# SUP_1_2_1_8.net
KiCad netlist of a schematic drawn in Altium Designer
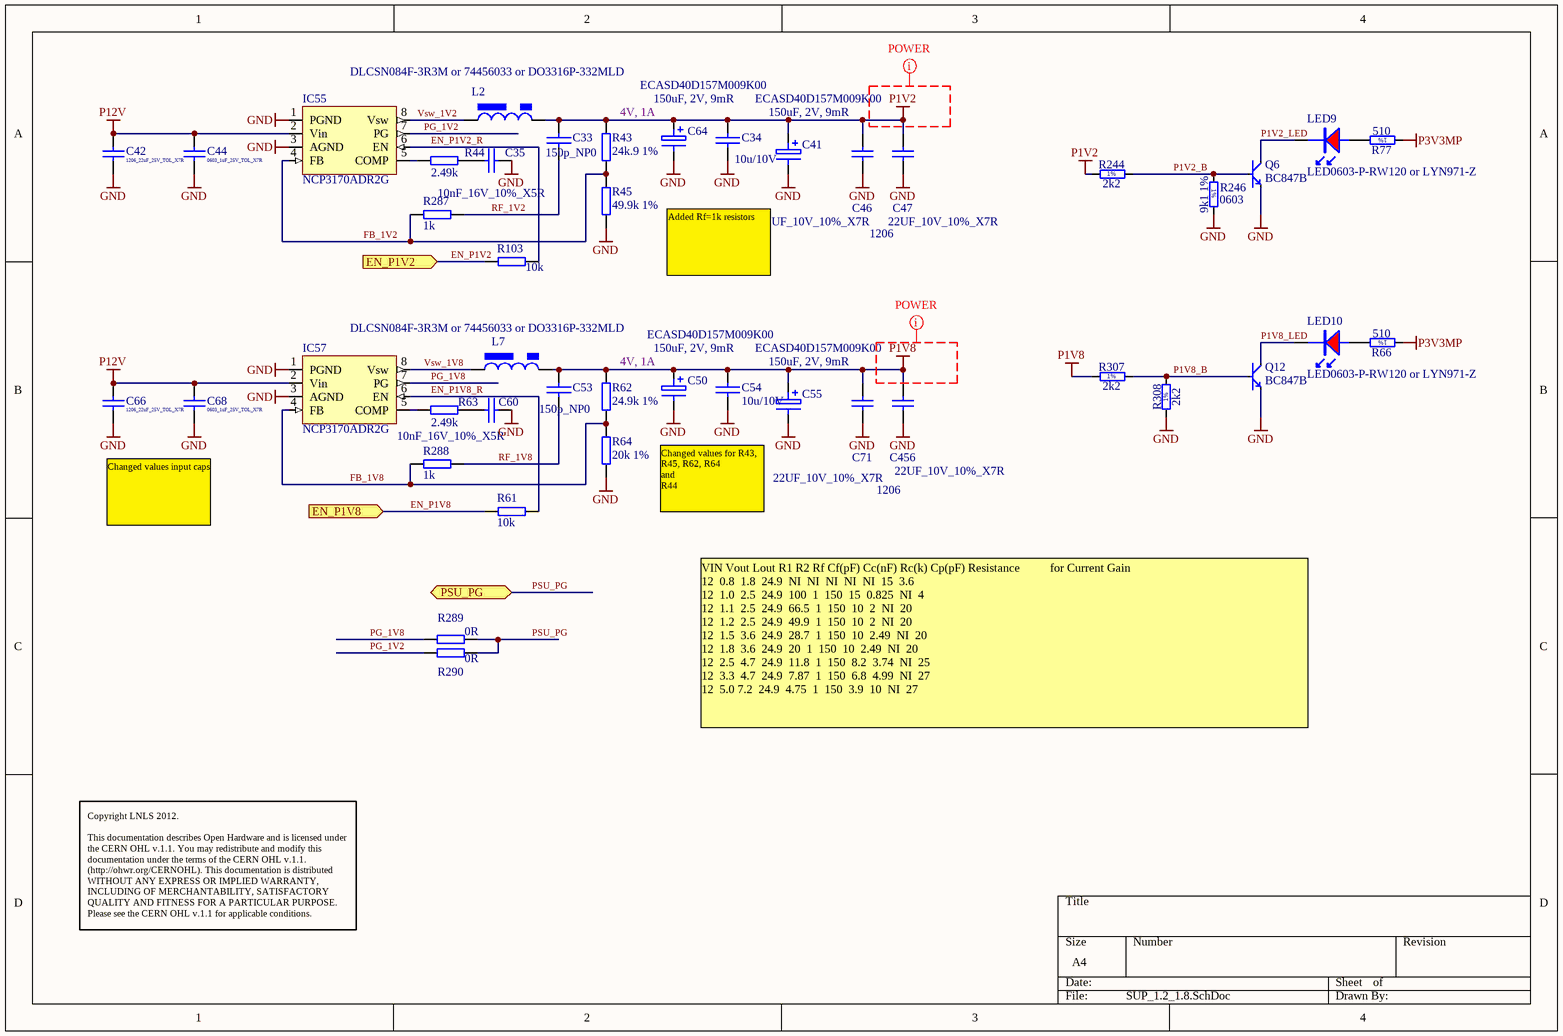
[diagram p0: SUP_1.2_1.8.SchDoc]

(export (version "E")
  (design (tool "Eeschema 10.0.6"))
  (components
    (comp (ref "C33")
      (value "150p_NP0")
      (footprint "0603C")
      (description "Capacitor SMD")
      (libsource (lib "LIBRARY_SCH") (part "CAP_SMD_0603"))
    )
    (comp (ref "C34")
      (value "10u/10V")
      (footprint "0805C")
      (description "Capacitor SMD")
      (libsource (lib "LIBRARY_SCH") (part "CAP_SMD_0805"))
    )
    (comp (ref "C35")
      (value "10nF_16V_10%_X5R")
      (footprint "0603C")
      (description "Capacitor SMD")
      (libsource (lib "LIBRARY_SCH") (part "CAP_SMD_0603"))
    )
    (comp (ref "C41")
      (value "ECASD40D157M009K00")
      (footprint "2917_POLY")
      (description "POLY, 150uF, 2V, ESR: 9mR")
      (fields (field (name "ALTIUM_VALUE") "150uF, 2V, 9mR"))
      (libsource (lib "LIBRARY_SCH") (part "CAP_POLYMER_SMDD"))
    )
    (comp (ref "C42")
      (value "1206_22uF_25V_TOL_X7R")
      (footprint "CAPC3225X140N")
      (fields (field (name "PART NUMBER") "Ceramic_1206"))
      (libsource (lib "Capacitors") (part "Capacitor"))
    )
    (comp (ref "C44")
      (value "0603_1uF_25V_TOL_X7R")
      (footprint "CAPC1608X90N")
      (fields (field (name "PART NUMBER") "Ceramic_0603"))
      (libsource (lib "Capacitors") (part "Capacitor"))
    )
    (comp (ref "C46")
      (value "22UF_10V_10%_X7R")
      (footprint "1206C")
      (description "Non-polarised capacitor")
      (fields
        (field (name "PART NUMBER") "CC1206_22UF_10V_10%_X7R")
        (field (name "VOLTAGE") "10V")
        (field (name "AUTHOR") "CERN DEM JLC")
      )
      (libsource (lib "Capacitors") (part "Capacitor - non polarized"))
    )
    (comp (ref "C47")
      (value "22UF_10V_10%_X7R")
      (footprint "1206C")
      (description "Non-polarised capacitor")
      (fields
        (field (name "PART NUMBER") "CC1206_22UF_10V_10%_X7R")
        (field (name "VOLTAGE") "10V")
        (field (name "CASE") "1206")
        (field (name "AUTHOR") "CERN DEM JLC")
      )
      (libsource (lib "Capacitors") (part "Capacitor - non polarized"))
    )
    (comp (ref "C50")
      (value "ECASD40D157M009K00")
      (footprint "2917_POLY")
      (description "POLY, 150uF, 2V, ESR: 9mR")
      (fields (field (name "ALTIUM_VALUE") "150uF, 2V, 9mR"))
      (libsource (lib "LIBRARY_SCH") (part "CAP_POLYMER_SMDD"))
    )
    (comp (ref "C53")
      (value "150p_NP0")
      (footprint "0603C")
      (description "Capacitor SMD")
      (libsource (lib "LIBRARY_SCH") (part "CAP_SMD_0603"))
    )
    (comp (ref "C54")
      (value "10u/10V")
      (footprint "0805C")
      (description "Capacitor SMD")
      (libsource (lib "LIBRARY_SCH") (part "CAP_SMD_0805"))
    )
    (comp (ref "C55")
      (value "ECASD40D157M009K00")
      (footprint "2917_POLY")
      (description "POLY, 150uF, 2V, ESR: 9mR")
      (fields (field (name "ALTIUM_VALUE") "150uF, 2V, 9mR"))
      (libsource (lib "LIBRARY_SCH") (part "CAP_POLYMER_SMDD"))
    )
    (comp (ref "C60")
      (value "10nF_16V_10%_X5R")
      (footprint "0603C")
      (description "Capacitor SMD")
      (libsource (lib "LIBRARY_SCH") (part "CAP_SMD_0603"))
    )
    (comp (ref "C64")
      (value "ECASD40D157M009K00")
      (footprint "2917_POLY")
      (description "POLY, 150uF, 2V, ESR: 9mR")
      (fields (field (name "ALTIUM_VALUE") "150uF, 2V, 9mR"))
      (libsource (lib "LIBRARY_SCH") (part "CAP_POLYMER_SMDD"))
    )
    (comp (ref "C66")
      (value "1206_22uF_25V_TOL_X7R")
      (footprint "CAPC3225X140N")
      (fields (field (name "PART NUMBER") "Ceramic_1206"))
      (libsource (lib "Capacitors") (part "Capacitor"))
    )
    (comp (ref "C68")
      (value "0603_1uF_25V_TOL_X7R")
      (footprint "CAPC1608X90N")
      (fields (field (name "PART NUMBER") "Ceramic_0603"))
      (libsource (lib "Capacitors") (part "Capacitor"))
    )
    (comp (ref "C71")
      (value "22UF_10V_10%_X7R")
      (footprint "1206C")
      (description "Non-polarised capacitor")
      (fields
        (field (name "PART NUMBER") "CC1206_22UF_10V_10%_X7R")
        (field (name "VOLTAGE") "10V")
        (field (name "AUTHOR") "CERN DEM JLC")
      )
      (libsource (lib "Capacitors") (part "Capacitor - non polarized"))
    )
    (comp (ref "C456")
      (value "22UF_10V_10%_X7R")
      (footprint "1206C")
      (description "Non-polarised capacitor")
      (fields
        (field (name "PART NUMBER") "CC1206_22UF_10V_10%_X7R")
        (field (name "VOLTAGE") "10V")
        (field (name "CASE") "1206")
        (field (name "AUTHOR") "CERN DEM JLC")
      )
      (libsource (lib "Capacitors") (part "Capacitor - non polarized"))
    )
    (comp (ref "IC55")
      (value "NCP3170ADR2G")
      (footprint "so-8")
      (description "4.5V to 18V, 3A synch buck")
      (libsource (lib "LIBRARY_SCH") (part "PWM_NCP3170"))
    )
    (comp (ref "IC57")
      (value "NCP3170ADR2G")
      (footprint "so-8")
      (description "4.5V to 18V, 3A synch buck")
      (libsource (lib "LIBRARY_SCH") (part "PWM_NCP3170"))
    )
    (comp (ref "L2")
      (value "DLCSN084F-3R3M or 74456033 or DO3316P-332MLD")
      (footprint "IND_CSN084F")
      (description "3.3uH, 20%, 5.4A, 0.015R")
      (libsource (lib "LIBRARY_SCH") (part "L_POWER_CSN084F_3R3"))
    )
    (comp (ref "L7")
      (value "DLCSN084F-3R3M or 74456033 or DO3316P-332MLD")
      (footprint "IND_CSN084F")
      (description "3.3uH, 20%, 5.4A, 0.015R")
      (libsource (lib "LIBRARY_SCH") (part "L_POWER_CSN084F_3R3"))
    )
    (comp (ref "LED9")
      (value "LED0603-P-RW120 or LYN971-Z")
      (footprint "led_0603R")
      (description "LED 0603 red")
      (libsource (lib "LIBRARY_SCH") (part "LED_0603R"))
    )
    (comp (ref "LED10")
      (value "LED0603-P-RW120 or LYN971-Z")
      (footprint "led_0603R")
      (description "LED 0603 red")
      (libsource (lib "LIBRARY_SCH") (part "LED_0603R"))
    )
    (comp (ref "Q6")
      (value "BC847B")
      (footprint "SOT-23")
      (description "Transistor")
      (libsource (lib "LIBRARY_SCH") (part "Q_BC847B"))
    )
    (comp (ref "Q12")
      (value "BC847B")
      (footprint "SOT-23")
      (description "Transistor")
      (libsource (lib "LIBRARY_SCH") (part "Q_BC847B"))
    )
    (comp (ref "R43")
      (value "24k.9 1%")
      (footprint "0603R")
      (description "SMD Resistor")
      (libsource (lib "LIBRARY_SCH") (part "RES_0603"))
    )
    (comp (ref "R44")
      (value "2.49k")
      (footprint "0603R")
      (description "SMD Resistor")
      (libsource (lib "LIBRARY_SCH") (part "RES_0603"))
    )
    (comp (ref "R45")
      (value "49.9k 1%")
      (footprint "0603R")
      (description "SMD Resistor")
      (libsource (lib "LIBRARY_SCH") (part "RES_0603"))
    )
    (comp (ref "R61")
      (value "10k")
      (footprint "0402R")
      (description "SMD Resistor")
      (libsource (lib "LIBRARY_SCH") (part "RES_SMD"))
    )
    (comp (ref "R62")
      (value "24.9k 1%")
      (footprint "0603R")
      (description "SMD Resistor")
      (libsource (lib "LIBRARY_SCH") (part "RES_0603"))
    )
    (comp (ref "R63")
      (value "2.49k")
      (footprint "0603R")
      (description "SMD Resistor")
      (libsource (lib "LIBRARY_SCH") (part "RES_0603"))
    )
    (comp (ref "R64")
      (value "20k 1%")
      (footprint "0603R")
      (description "SMD Resistor")
      (libsource (lib "LIBRARY_SCH") (part "RES_0603"))
    )
    (comp (ref "R66")
      (value "510")
      (footprint "0603R")
      (description "Resistor - 1%")
      (fields
        (field (name "PART NUMBER") "R0402_510R_1%_0.0625W_100PPM")
        (field (name "POWER") "0.0625W")
        (field (name "AUTHOR") "CERN DEM JLC")
      )
      (libsource (lib "Resistors") (part "Resistor - 1%"))
    )
    (comp (ref "R77")
      (value "510")
      (footprint "0603R")
      (description "Resistor - 1%")
      (fields
        (field (name "PART NUMBER") "R0402_510R_1%_0.0625W_100PPM")
        (field (name "POWER") "0.0625W")
        (field (name "AUTHOR") "CERN DEM JLC")
      )
      (libsource (lib "Resistors") (part "Resistor - 1%"))
    )
    (comp (ref "R103")
      (value "10k")
      (footprint "0402R")
      (description "SMD Resistor")
      (libsource (lib "LIBRARY_SCH") (part "RES_SMD"))
    )
    (comp (ref "R244")
      (value "2k2")
      (footprint "RESC1608X55N")
      (description "Resistor - 1%")
      (fields
        (field (name "PART NUMBER") "R0603_2K2_1%_0.1W_100PPM")
        (field (name "POWER") "0.1W")
        (field (name "AUTHOR") "CERN DEM JLC")
      )
      (libsource (lib "Resistors") (part "Resistor - 1%"))
    )
    (comp (ref "R246")
      (value "9k1 1%")
      (footprint "0603R")
      (description "Resistor - 1%")
      (fields
        (field (name "PART NUMBER") "R0603_9K1_1%_0.1W_100PPM")
        (field (name "POWER") "0.1W")
        (field (name "CASE") "0603")
        (field (name "AUTHOR") "CERN DEM JLC")
      )
      (libsource (lib "Resistors") (part "Resistor - 1%"))
    )
    (comp (ref "R287")
      (value "1k")
      (footprint "0603R")
      (description "SMD Resistor")
      (libsource (lib "LIBRARY_SCH") (part "RES_0603"))
    )
    (comp (ref "R288")
      (value "1k")
      (footprint "0603R")
      (description "SMD Resistor")
      (libsource (lib "LIBRARY_SCH") (part "RES_0603"))
    )
    (comp (ref "R289")
      (value "0R")
      (footprint "0402R")
      (description "SMD Resistor")
      (libsource (lib "LIBRARY_SCH") (part "RES_0402"))
    )
    (comp (ref "R290")
      (value "0R")
      (footprint "0402R")
      (description "SMD Resistor")
      (libsource (lib "LIBRARY_SCH") (part "RES_0402"))
    )
    (comp (ref "R307")
      (value "2k2")
      (footprint "RESC1608X55N")
      (description "Resistor - 1%")
      (fields
        (field (name "PART NUMBER") "R0603_2K2_1%_0.1W_100PPM")
        (field (name "POWER") "0.1W")
        (field (name "AUTHOR") "CERN DEM JLC")
      )
      (libsource (lib "Resistors") (part "Resistor - 1%"))
    )
    (comp (ref "R308")
      (value "2k2")
      (footprint "RESC1608X55N")
      (description "Resistor - 1%")
      (fields
        (field (name "PART NUMBER") "R0603_2K2_1%_0.1W_100PPM")
        (field (name "POWER") "0.1W")
        (field (name "AUTHOR") "CERN DEM JLC")
      )
      (libsource (lib "Resistors") (part "Resistor - 1%"))
    )
  )
  (nets
    (net (code "1") (name "/EN_P1V2") (class "Default")
      (node (ref "R103") (pin "1") (pinfunction "1_1") (pintype "passive"))
    )
    (net (code "2") (name "/EN_P1V2_R") (class "Default")
      (node (ref "IC55") (pin "6") (pinfunction "EN_6") (pintype "input"))
      (node (ref "R103") (pin "2") (pinfunction "2_2") (pintype "passive"))
    )
    (net (code "3") (name "/EN_P1V8") (class "Default")
      (node (ref "R61") (pin "1") (pinfunction "1_1") (pintype "passive"))
    )
    (net (code "4") (name "/EN_P1V8_R") (class "Default")
      (node (ref "IC57") (pin "6") (pinfunction "EN_6") (pintype "input"))
      (node (ref "R61") (pin "2") (pinfunction "2_2") (pintype "passive"))
    )
    (net (code "5") (name "/FB_1V2") (class "Default")
      (node (ref "IC55") (pin "4") (pinfunction "FB_4") (pintype "input"))
      (node (ref "R287") (pin "2") (pinfunction "2_2") (pintype "passive"))
      (node (ref "R43") (pin "1") (pinfunction "1_1") (pintype "passive"))
      (node (ref "R45") (pin "2") (pinfunction "2_2") (pintype "passive"))
    )
    (net (code "6") (name "/FB_1V8") (class "Default")
      (node (ref "IC57") (pin "4") (pinfunction "FB_4") (pintype "input"))
      (node (ref "R288") (pin "2") (pinfunction "2_2") (pintype "passive"))
      (node (ref "R62") (pin "1") (pinfunction "1_1") (pintype "passive"))
      (node (ref "R64") (pin "2") (pinfunction "2_2") (pintype "passive"))
    )
    (net (code "7") (name "/P1V2_B") (class "Default")
      (node (ref "Q6") (pin "1") (pinfunction "B_1") (pintype "passive"))
      (node (ref "R244") (pin "2") (pinfunction "2_2") (pintype "passive"))
      (node (ref "R246") (pin "1") (pinfunction "1_1") (pintype "passive"))
    )
    (net (code "8") (name "/P1V2_LED") (class "Default")
      (node (ref "LED9") (pin "K") (pinfunction "K_K") (pintype "passive"))
      (node (ref "Q6") (pin "3") (pinfunction "C_3") (pintype "passive"))
    )
    (net (code "9") (name "/P1V8_B") (class "Default")
      (node (ref "Q12") (pin "1") (pinfunction "B_1") (pintype "passive"))
      (node (ref "R307") (pin "2") (pinfunction "2_2") (pintype "passive"))
      (node (ref "R308") (pin "2") (pinfunction "2_2") (pintype "passive"))
    )
    (net (code "10") (name "/P1V8_LED") (class "Default")
      (node (ref "LED10") (pin "K") (pinfunction "K_K") (pintype "passive"))
      (node (ref "Q12") (pin "3") (pinfunction "C_3") (pintype "passive"))
    )
    (net (code "11") (name "/PG_1V2") (class "Default")
      (node (ref "IC55") (pin "7") (pinfunction "PG_7") (pintype "output"))
      (node (ref "R290") (pin "2") (pinfunction "2_2") (pintype "passive"))
    )
    (net (code "12") (name "/PG_1V8") (class "Default")
      (node (ref "IC57") (pin "7") (pinfunction "PG_7") (pintype "output"))
      (node (ref "R289") (pin "2") (pinfunction "2_2") (pintype "passive"))
    )
    (net (code "13") (name "/PSU_PG") (class "Default")
      (node (ref "R289") (pin "1") (pinfunction "1_1") (pintype "passive"))
      (node (ref "R290") (pin "1") (pinfunction "1_1") (pintype "passive"))
    )
    (net (code "14") (name "/RF_1V2") (class "Default")
      (node (ref "C33") (pin "2") (pinfunction "2_2") (pintype "passive"))
      (node (ref "R287") (pin "1") (pinfunction "1_1") (pintype "passive"))
    )
    (net (code "15") (name "/RF_1V8") (class "Default")
      (node (ref "C53") (pin "2") (pinfunction "2_2") (pintype "passive"))
      (node (ref "R288") (pin "1") (pinfunction "1_1") (pintype "passive"))
    )
    (net (code "16") (name "/Vsw_1V2") (class "Default")
      (node (ref "IC55") (pin "8") (pinfunction "Vsw_8") (pintype "output"))
      (node (ref "L2") (pin "1") (pintype "passive"))
    )
    (net (code "17") (name "/Vsw_1V8") (class "Default")
      (node (ref "IC57") (pin "8") (pinfunction "Vsw_8") (pintype "output"))
      (node (ref "L7") (pin "1") (pintype "passive"))
    )
    (net (code "18") (name "GND") (class "Default")
      (node (ref "C34") (pin "2") (pinfunction "2_2") (pintype "passive"))
      (node (ref "C35") (pin "2") (pinfunction "2_2") (pintype "passive"))
      (node (ref "C41") (pin "2") (pinfunction "2_2") (pintype "passive"))
      (node (ref "C42") (pin "1") (pinfunction "1_1") (pintype "passive"))
      (node (ref "C44") (pin "1") (pinfunction "1_1") (pintype "passive"))
      (node (ref "C456") (pin "2") (pinfunction "2_2") (pintype "passive"))
      (node (ref "C46") (pin "2") (pinfunction "2_2") (pintype "passive"))
      (node (ref "C47") (pin "2") (pinfunction "2_2") (pintype "passive"))
      (node (ref "C50") (pin "2") (pinfunction "2_2") (pintype "passive"))
      (node (ref "C54") (pin "2") (pinfunction "2_2") (pintype "passive"))
      (node (ref "C55") (pin "2") (pinfunction "2_2") (pintype "passive"))
      (node (ref "C60") (pin "2") (pinfunction "2_2") (pintype "passive"))
      (node (ref "C64") (pin "2") (pinfunction "2_2") (pintype "passive"))
      (node (ref "C66") (pin "1") (pinfunction "1_1") (pintype "passive"))
      (node (ref "C68") (pin "1") (pinfunction "1_1") (pintype "passive"))
      (node (ref "C71") (pin "2") (pinfunction "2_2") (pintype "passive"))
      (node (ref "IC55") (pin "1") (pinfunction "PGND_1") (pintype "power_in"))
      (node (ref "IC55") (pin "3") (pinfunction "AGND_3") (pintype "power_in"))
      (node (ref "IC57") (pin "1") (pinfunction "PGND_1") (pintype "power_in"))
      (node (ref "IC57") (pin "3") (pinfunction "AGND_3") (pintype "power_in"))
      (node (ref "Q12") (pin "2") (pinfunction "E_2") (pintype "passive"))
      (node (ref "Q6") (pin "2") (pinfunction "E_2") (pintype "passive"))
      (node (ref "R246") (pin "2") (pinfunction "2_2") (pintype "passive"))
      (node (ref "R308") (pin "1") (pinfunction "1_1") (pintype "passive"))
      (node (ref "R45") (pin "1") (pinfunction "1_1") (pintype "passive"))
      (node (ref "R64") (pin "1") (pinfunction "1_1") (pintype "passive"))
    )
    (net (code "19") (name "Net-(C35-Pad1)") (class "Default")
      (node (ref "C35") (pin "1") (pinfunction "1_1") (pintype "passive"))
      (node (ref "R44") (pin "1") (pinfunction "1_1") (pintype "passive"))
    )
    (net (code "20") (name "Net-(C60-Pad1)") (class "Default")
      (node (ref "C60") (pin "1") (pinfunction "1_1") (pintype "passive"))
      (node (ref "R63") (pin "1") (pinfunction "1_1") (pintype "passive"))
    )
    (net (code "21") (name "Net-(IC55-COMP)") (class "Default")
      (node (ref "IC55") (pin "5") (pinfunction "COMP_5") (pintype "passive"))
      (node (ref "R44") (pin "2") (pinfunction "2_2") (pintype "passive"))
    )
    (net (code "22") (name "Net-(IC57-COMP)") (class "Default")
      (node (ref "IC57") (pin "5") (pinfunction "COMP_5") (pintype "passive"))
      (node (ref "R63") (pin "2") (pinfunction "2_2") (pintype "passive"))
    )
    (net (code "23") (name "Net-(LED9-PadA)") (class "Default")
      (node (ref "LED9") (pin "A") (pinfunction "A_A") (pintype "passive"))
      (node (ref "R77") (pin "2") (pinfunction "2_2") (pintype "passive"))
    )
    (net (code "24") (name "Net-(LED10-PadA)") (class "Default")
      (node (ref "LED10") (pin "A") (pinfunction "A_A") (pintype "passive"))
      (node (ref "R66") (pin "2") (pinfunction "2_2") (pintype "passive"))
    )
    (net (code "25") (name "P1V2") (class "Default")
      (node (ref "C33") (pin "1") (pinfunction "1_1") (pintype "passive"))
      (node (ref "C34") (pin "1") (pinfunction "1_1") (pintype "passive"))
      (node (ref "C41") (pin "1") (pinfunction "1_1") (pintype "passive"))
      (node (ref "C46") (pin "1") (pinfunction "1_1") (pintype "passive"))
      (node (ref "C47") (pin "1") (pinfunction "1_1") (pintype "passive"))
      (node (ref "C64") (pin "1") (pinfunction "1_1") (pintype "passive"))
      (node (ref "L2") (pin "2") (pintype "passive"))
      (node (ref "R244") (pin "1") (pinfunction "1_1") (pintype "passive"))
      (node (ref "R43") (pin "2") (pinfunction "2_2") (pintype "passive"))
    )
    (net (code "26") (name "P1V8") (class "Default")
      (node (ref "C456") (pin "1") (pinfunction "1_1") (pintype "passive"))
      (node (ref "C50") (pin "1") (pinfunction "1_1") (pintype "passive"))
      (node (ref "C53") (pin "1") (pinfunction "1_1") (pintype "passive"))
      (node (ref "C54") (pin "1") (pinfunction "1_1") (pintype "passive"))
      (node (ref "C55") (pin "1") (pinfunction "1_1") (pintype "passive"))
      (node (ref "C71") (pin "1") (pinfunction "1_1") (pintype "passive"))
      (node (ref "L7") (pin "2") (pintype "passive"))
      (node (ref "R307") (pin "1") (pinfunction "1_1") (pintype "passive"))
      (node (ref "R62") (pin "2") (pinfunction "2_2") (pintype "passive"))
    )
    (net (code "27") (name "P3V3MP") (class "Default")
      (node (ref "R66") (pin "1") (pinfunction "1_1") (pintype "passive"))
      (node (ref "R77") (pin "1") (pinfunction "1_1") (pintype "passive"))
    )
    (net (code "28") (name "P12V") (class "Default")
      (node (ref "C42") (pin "2") (pinfunction "2_2") (pintype "passive"))
      (node (ref "C44") (pin "2") (pinfunction "2_2") (pintype "passive"))
      (node (ref "C66") (pin "2") (pinfunction "2_2") (pintype "passive"))
      (node (ref "C68") (pin "2") (pinfunction "2_2") (pintype "passive"))
      (node (ref "IC55") (pin "2") (pinfunction "Vin_2") (pintype "power_in"))
      (node (ref "IC57") (pin "2") (pinfunction "Vin_2") (pintype "power_in"))
    )
  )
)
